# subtractor_single.net
KiCad netlist of a schematic drawn in Altium Designer
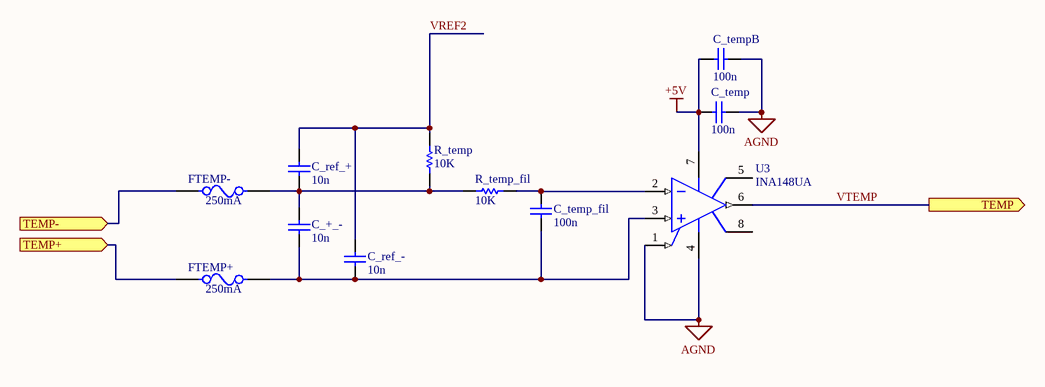
[diagram p0: subtractor_single.SchDoc]

(export (version "E")
  (design (tool "Eeschema 10.0.6"))
  (components
    (comp (ref "C_+_-")
      (value "10n")
      (footprint "CAPC0603(1608)55_N")
      (description "Keramikvielschichtkondensator, SMD, Baureihe MC, ± 10%")
      (fields (field (name "MANUFACTURER") "TDK") (field (name "TOLERANCE") "± 10%"))
      (libsource (lib "Res&Caps") (part "Cap 10n"))
    )
    (comp (ref "C_ref_+")
      (value "10n")
      (footprint "CAPC0603(1608)55_N")
      (description "Keramikvielschichtkondensator, SMD, Baureihe MC, ± 10%")
      (fields (field (name "MANUFACTURER") "TDK") (field (name "TOLERANCE") "± 10%"))
      (libsource (lib "Res&Caps") (part "Cap 10n"))
    )
    (comp (ref "C_ref_-")
      (value "10n")
      (footprint "CAPC0603(1608)55_N")
      (description "Keramikvielschichtkondensator, SMD, Baureihe MC, ± 10%")
      (fields (field (name "MANUFACTURER") "TDK") (field (name "TOLERANCE") "± 10%"))
      (libsource (lib "Res&Caps") (part "Cap 10n"))
    )
    (comp (ref "C_temp")
      (value "100n")
      (footprint "CAPC0603(1608)55_N")
      (description "Keramikvielschichtkondensator, SMD, Baureihe MC, ± 10%")
      (fields (field (name "MANUFACTURER") "TDK") (field (name "TOLERANCE") "± 10%"))
      (libsource (lib "Res&Caps") (part "Cap 100n"))
    )
    (comp (ref "C_tempB")
      (value "100n")
      (footprint "CAPC0603(1608)55_N")
      (description "Keramikvielschichtkondensator, SMD, Baureihe MC, ± 10%")
      (fields (field (name "MANUFACTURER") "TDK") (field (name "TOLERANCE") "± 10%"))
      (libsource (lib "Res&Caps") (part "Cap 100n"))
    )
    (comp (ref "C_temp_fil")
      (value "100n")
      (footprint "CAPC0603(1608)55_N")
      (description "Keramikvielschichtkondensator, SMD, Baureihe MC, ± 10%")
      (fields (field (name "MANUFACTURER") "TDK") (field (name "TOLERANCE") "± 10%"))
      (libsource (lib "Res&Caps") (part "Cap 100n"))
    )
    (comp (ref "FTEMP+")
      (value "250mA")
      (footprint "RESC0603(1608)_N")
      (description "Fuse, Fast Blow 250mA, 63VDC")
      (fields (field (name "MANUFACTURER") "Bel Fuse"))
      (libsource (lib "LV-BMS") (part "Bel Fuse C2Q250"))
    )
    (comp (ref "FTEMP-")
      (value "250mA")
      (footprint "RESC0603(1608)_N")
      (description "Fuse, Fast Blow 250mA, 63VDC")
      (fields (field (name "MANUFACTURER") "Bel Fuse"))
      (libsource (lib "LV-BMS") (part "Bel Fuse C2Q250"))
    )
    (comp (ref "R_temp")
      (value "10K")
      (footprint "RESC0603(1608)_N")
      (description "Chipwiderstand, SMD, Baureihe MC, 1%")
      (fields (field (name "MANUFACTURER") "Multicomp") (field (name "POWER") "100mW"))
      (libsource (lib "Res&Caps") (part "Res 10K"))
    )
    (comp (ref "R_temp_fil")
      (value "10K")
      (footprint "RESC0603(1608)_N")
      (description "Chipwiderstand, SMD, Baureihe MC, 1%")
      (fields (field (name "MANUFACTURER") "Multicomp") (field (name "POWER") "100mW"))
      (libsource (lib "Res&Caps") (part "Res 10K"))
    )
    (comp (ref "U3")
      (value "INA148UA")
      (footprint "D0008A_N")
      (fields (field (name "MANUFACTURER") "Texas Instruments"))
      (libsource (lib "Altium Content Vault") (part "TI-INA148_148-Q1D8"))
    )
  )
  (nets
    (net (code "1") (name "+5V") (class "Default")
      (node (ref "C_temp") (pin "1") (pinfunction "1_1") (pintype "passive"))
      (node (ref "C_tempB") (pin "1") (pinfunction "1_1") (pintype "passive"))
      (node (ref "U3") (pin "7") (pinfunction "V+_7") (pintype "power_in"))
    )
    (net (code "2") (name "/TEMP+") (class "Default")
      (node (ref "FTEMP+") (pin "1") (pinfunction "1_1") (pintype "passive"))
    )
    (net (code "3") (name "/TEMP-") (class "Default")
      (node (ref "FTEMP-") (pin "1") (pinfunction "1_1") (pintype "passive"))
    )
    (net (code "4") (name "/VREF2") (class "Default")
      (node (ref "C_ref_+") (pin "2") (pinfunction "2_2") (pintype "passive"))
      (node (ref "C_ref_-") (pin "2") (pinfunction "2_2") (pintype "passive"))
      (node (ref "R_temp") (pin "2") (pinfunction "2_2") (pintype "passive"))
    )
    (net (code "5") (name "/VTEMP") (class "Default")
      (node (ref "U3") (pin "6") (pinfunction "OUT_6") (pintype "output"))
    )
    (net (code "6") (name "AGND") (class "Default")
      (node (ref "C_temp") (pin "2") (pinfunction "2_2") (pintype "passive"))
      (node (ref "C_tempB") (pin "2") (pinfunction "2_2") (pintype "passive"))
      (node (ref "U3") (pin "1") (pinfunction "REF_1") (pintype "input"))
      (node (ref "U3") (pin "4") (pinfunction "V-_4") (pintype "power_in"))
    )
    (net (code "7") (name "Net-(C_+_--Pad2)") (class "Default")
      (node (ref "C_+_-") (pin "2") (pinfunction "2_2") (pintype "passive"))
      (node (ref "C_ref_+") (pin "1") (pinfunction "1_1") (pintype "passive"))
      (node (ref "FTEMP-") (pin "2") (pinfunction "2_2") (pintype "passive"))
      (node (ref "R_temp") (pin "1") (pinfunction "1_1") (pintype "passive"))
      (node (ref "R_temp_fil") (pin "2") (pinfunction "2_2") (pintype "passive"))
    )
    (net (code "8") (name "Net-(U3-IN+)") (class "Default")
      (node (ref "C_+_-") (pin "1") (pinfunction "1_1") (pintype "passive"))
      (node (ref "C_ref_-") (pin "1") (pinfunction "1_1") (pintype "passive"))
      (node (ref "C_temp_fil") (pin "1") (pinfunction "1_1") (pintype "passive"))
      (node (ref "FTEMP+") (pin "2") (pinfunction "2_2") (pintype "passive"))
      (node (ref "U3") (pin "3") (pinfunction "IN+_3") (pintype "input"))
    )
    (net (code "9") (name "Net-(U3-IN-)") (class "Default")
      (node (ref "C_temp_fil") (pin "2") (pinfunction "2_2") (pintype "passive"))
      (node (ref "R_temp_fil") (pin "1") (pinfunction "1_1") (pintype "passive"))
      (node (ref "U3") (pin "2") (pinfunction "IN-_2") (pintype "input"))
    )
    (net (code "10") (name "unconnected-(U3-NC-Pad5)") (class "Default")
      (node (ref "U3") (pin "5") (pinfunction "NC_5") (pintype "passive"))
    )
    (net (code "11") (name "unconnected-(U3-NC-Pad8)") (class "Default")
      (node (ref "U3") (pin "8") (pinfunction "NC_8") (pintype "passive"))
    )
  )
)
